# FinalSchematic_FrankensToy_FabAcademy201.net
KiCad netlist of a schematic drawn in EAGLE
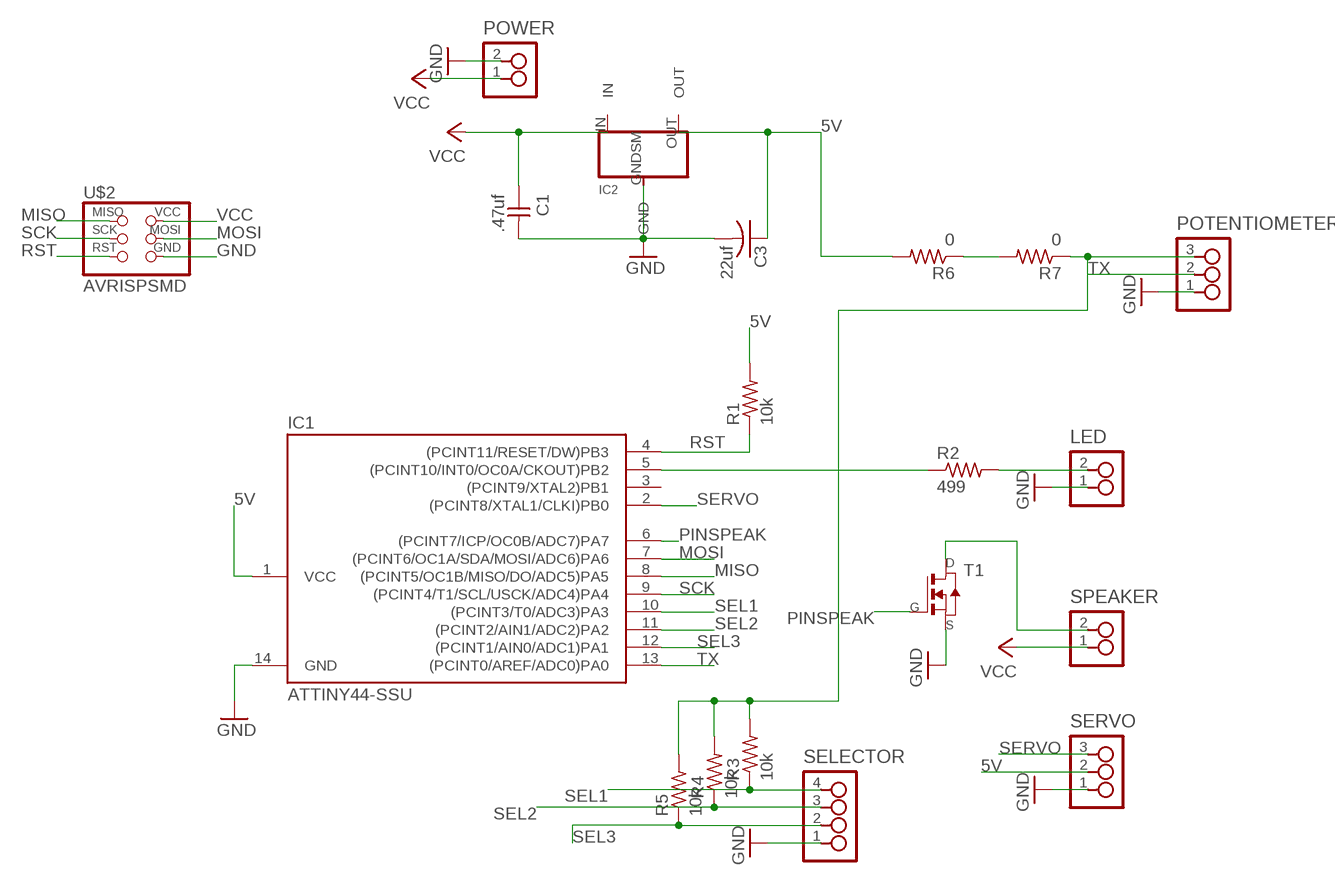
[diagram p0: schematic, sheet 1]

(export (version "E")
  (design (tool "Eeschema 10.0.6"))
  (components
    (comp (ref "C1")
      (value ".47uf")
      (footprint "eagle-import:1206")
      (libsource (lib "eagle-import") (part "UNPOLARIZED_CAPACITOR1206"))
    )
    (comp (ref "C3")
      (value "22uf")
      (footprint "eagle-import:C1206")
      (libsource (lib "eagle-import") (part "C-USC1206"))
    )
    (comp (ref "IC1")
      (value "ATTINY44-SSU")
      (footprint "eagle-import:SOIC14")
      (libsource (lib "eagle-import") (part "ATTINY44-SSU"))
    )
    (comp (ref "IC2")
      (value "REGULATOR")
      (footprint "eagle-import:SOT223")
      (libsource (lib "eagle-import") (part "REGULATOR"))
    )
    (comp (ref "LED")
      (value "2_PIN_HEADERHEADER")
      (footprint "eagle-import:SMT_PINS_2")
      (libsource (lib "eagle-import") (part "2_PIN_HEADERHEADER"))
    )
    (comp (ref "POTENTIOMETER")
      (value "3_PIN_HEADERHEADER")
      (footprint "eagle-import:SMT_PINS_3")
      (libsource (lib "eagle-import") (part "3_PIN_HEADERHEADER"))
    )
    (comp (ref "POWER")
      (value "2_PIN_HEADERHEADER")
      (footprint "eagle-import:SMT_PINS_2")
      (libsource (lib "eagle-import") (part "2_PIN_HEADERHEADER"))
    )
    (comp (ref "R1")
      (value "10k")
      (footprint "eagle-import:R1206")
      (libsource (lib "eagle-import") (part "R-US_R1206"))
    )
    (comp (ref "R2")
      (value "499")
      (footprint "eagle-import:1206")
      (libsource (lib "eagle-import") (part "RESISTOR1206"))
    )
    (comp (ref "R3")
      (value "10k")
      (footprint "eagle-import:R1206")
      (libsource (lib "eagle-import") (part "R-US_R1206"))
    )
    (comp (ref "R4")
      (value "10k")
      (footprint "eagle-import:R1206")
      (libsource (lib "eagle-import") (part "R-US_R1206"))
    )
    (comp (ref "R5")
      (value "10k")
      (footprint "eagle-import:R1206")
      (libsource (lib "eagle-import") (part "R-US_R1206"))
    )
    (comp (ref "R6")
      (value "0")
      (footprint "eagle-import:R1206")
      (libsource (lib "eagle-import") (part "R-US_R1206"))
    )
    (comp (ref "R7")
      (value "0")
      (footprint "eagle-import:R1206")
      (libsource (lib "eagle-import") (part "R-US_R1206"))
    )
    (comp (ref "SELECTOR")
      (value "4_PIN_HEADERHEADER")
      (footprint "eagle-import:SMT_PINS_4")
      (libsource (lib "eagle-import") (part "4_PIN_HEADERHEADER"))
    )
    (comp (ref "SERVO")
      (value "3_PIN_HEADERHEADER")
      (footprint "eagle-import:SMT_PINS_3")
      (libsource (lib "eagle-import") (part "3_PIN_HEADERHEADER"))
    )
    (comp (ref "SPEAKER")
      (value "2_PIN_HEADERHEADER")
      (footprint "eagle-import:SMT_PINS_2")
      (libsource (lib "eagle-import") (part "2_PIN_HEADERHEADER"))
    )
    (comp (ref "T1")
      (value "NMOSFETSOT23")
      (footprint "eagle-import:SOT-23")
      (libsource (lib "eagle-import") (part "NMOSFETSOT23"))
    )
    (comp (ref "U$2")
      (value "AVRISPSMD")
      (footprint "eagle-import:2X03SMD")
      (libsource (lib "eagle-import") (part "AVRISPSMD"))
    )
  )
  (nets
    (net (code "1") (name "/5V") (class "Default")
      (node (ref "C3") (pin "1") (pinfunction "1_1") (pintype "passive"))
      (node (ref "IC1") (pin "1") (pinfunction "VCC_1") (pintype "power_in"))
      (node (ref "IC2") (pin "OUT") (pinfunction "OUT_OUT") (pintype "bidirectional"))
      (node (ref "R1") (pin "2") (pinfunction "2_2") (pintype "passive"))
      (node (ref "R6") (pin "2") (pinfunction "2_2") (pintype "passive"))
      (node (ref "SERVO") (pin "2") (pinfunction "P$2_2") (pintype "bidirectional"))
    )
    (net (code "2") (name "/MISO") (class "Default")
      (node (ref "IC1") (pin "8") (pinfunction "(PCINT5/OC1B/MISO/DO/ADC5)PA5_8") (pintype "bidirectional"))
      (node (ref "U$2") (pin "1") (pinfunction "MISO_1") (pintype "passive"))
    )
    (net (code "3") (name "/MOSI") (class "Default")
      (node (ref "IC1") (pin "7") (pinfunction "(PCINT6/OC1A/SDA/MOSI/ADC6)PA6_7") (pintype "bidirectional"))
      (node (ref "U$2") (pin "4") (pinfunction "MOSI_4") (pintype "passive"))
    )
    (net (code "4") (name "/PINSPEAK") (class "Default")
      (node (ref "IC1") (pin "6") (pinfunction "(PCINT7/ICP/OC0B/ADC7)PA7_6") (pintype "bidirectional"))
      (node (ref "T1") (pin "3") (pinfunction "G_3") (pintype "passive"))
    )
    (net (code "5") (name "/RST") (class "Default")
      (node (ref "IC1") (pin "4") (pinfunction "(PCINT11/RESET/DW)PB3_4") (pintype "bidirectional"))
      (node (ref "R1") (pin "1") (pinfunction "1_1") (pintype "passive"))
      (node (ref "U$2") (pin "5") (pinfunction "RST_5") (pintype "passive"))
    )
    (net (code "6") (name "/SCK") (class "Default")
      (node (ref "IC1") (pin "9") (pinfunction "(PCINT4/T1/SCL/USCK/ADC4)PA4_9") (pintype "bidirectional"))
      (node (ref "U$2") (pin "3") (pinfunction "SCK_3") (pintype "passive"))
    )
    (net (code "7") (name "/SEL1") (class "Default")
      (node (ref "IC1") (pin "10") (pinfunction "(PCINT3/T0/ADC3)PA3_10") (pintype "bidirectional"))
      (node (ref "R3") (pin "1") (pinfunction "1_1") (pintype "passive"))
      (node (ref "SELECTOR") (pin "4") (pinfunction "P$4_4") (pintype "bidirectional"))
    )
    (net (code "8") (name "/SEL2") (class "Default")
      (node (ref "IC1") (pin "11") (pinfunction "(PCINT2/AIN1/ADC2)PA2_11") (pintype "bidirectional"))
      (node (ref "R4") (pin "1") (pinfunction "1_1") (pintype "passive"))
      (node (ref "SELECTOR") (pin "3") (pinfunction "P$3_3") (pintype "bidirectional"))
    )
    (net (code "9") (name "/SEL3") (class "Default")
      (node (ref "IC1") (pin "12") (pinfunction "(PCINT1/AIN0/ADC1)PA1_12") (pintype "bidirectional"))
      (node (ref "R5") (pin "1") (pinfunction "1_1") (pintype "passive"))
      (node (ref "SELECTOR") (pin "2") (pinfunction "P$2_2") (pintype "bidirectional"))
    )
    (net (code "10") (name "/SERVO") (class "Default")
      (node (ref "IC1") (pin "2") (pinfunction "(PCINT8/XTAL1/CLKI)PB0_2") (pintype "bidirectional"))
      (node (ref "SERVO") (pin "3") (pinfunction "P$3_3") (pintype "bidirectional"))
    )
    (net (code "11") (name "/TX") (class "Default")
      (node (ref "IC1") (pin "13") (pinfunction "(PCINT0/AREF/ADC0)PA0_13") (pintype "bidirectional"))
      (node (ref "POTENTIOMETER") (pin "2") (pinfunction "P$2_2") (pintype "bidirectional"))
    )
    (net (code "12") (name "GND") (class "Default")
      (node (ref "C1") (pin "2") (pinfunction "2_2") (pintype "passive"))
      (node (ref "C3") (pin "2") (pinfunction "2_2") (pintype "passive"))
      (node (ref "IC1") (pin "14") (pinfunction "GND_14") (pintype "power_in"))
      (node (ref "IC2") (pin "GNDSM") (pinfunction "GND_GNDSM") (pintype "bidirectional"))
      (node (ref "LED") (pin "1") (pinfunction "1_1") (pintype "bidirectional"))
      (node (ref "POTENTIOMETER") (pin "1") (pinfunction "P$1_1") (pintype "bidirectional"))
      (node (ref "POWER") (pin "2") (pinfunction "2_2") (pintype "bidirectional"))
      (node (ref "SELECTOR") (pin "1") (pinfunction "P$1_1") (pintype "bidirectional"))
      (node (ref "SERVO") (pin "1") (pinfunction "P$1_1") (pintype "bidirectional"))
      (node (ref "T1") (pin "2") (pinfunction "S_2") (pintype "passive"))
      (node (ref "U$2") (pin "6") (pinfunction "GND_6") (pintype "passive"))
    )
    (net (code "13") (name "Net-(IC1-(PCINT10{slash}INT0{slash}OC0A{slash}CKOUT)PB2)") (class "Default")
      (node (ref "IC1") (pin "5") (pinfunction "(PCINT10/INT0/OC0A/CKOUT)PB2_5") (pintype "bidirectional"))
      (node (ref "R2") (pin "1") (pinfunction "1_1") (pintype "passive"))
    )
    (net (code "14") (name "Net-(LED-Pad2)") (class "Default")
      (node (ref "LED") (pin "2") (pinfunction "2_2") (pintype "bidirectional"))
      (node (ref "R2") (pin "2") (pinfunction "2_2") (pintype "passive"))
    )
    (net (code "15") (name "Net-(POTENTIOMETER-P$3)") (class "Default")
      (node (ref "POTENTIOMETER") (pin "3") (pinfunction "P$3_3") (pintype "bidirectional"))
      (node (ref "R3") (pin "2") (pinfunction "2_2") (pintype "passive"))
      (node (ref "R4") (pin "2") (pinfunction "2_2") (pintype "passive"))
      (node (ref "R5") (pin "2") (pinfunction "2_2") (pintype "passive"))
      (node (ref "R7") (pin "1") (pinfunction "1_1") (pintype "passive"))
    )
    (net (code "16") (name "Net-(R6-Pad1)") (class "Default")
      (node (ref "R6") (pin "1") (pinfunction "1_1") (pintype "passive"))
      (node (ref "R7") (pin "2") (pinfunction "2_2") (pintype "passive"))
    )
    (net (code "17") (name "Net-(T1-D)") (class "Default")
      (node (ref "SPEAKER") (pin "2") (pinfunction "2_2") (pintype "bidirectional"))
      (node (ref "T1") (pin "1") (pinfunction "D_1") (pintype "passive"))
    )
    (net (code "18") (name "VCC") (class "Default")
      (node (ref "C1") (pin "1") (pinfunction "1_1") (pintype "passive"))
      (node (ref "IC2") (pin "IN") (pinfunction "IN_IN") (pintype "bidirectional"))
      (node (ref "POWER") (pin "1") (pinfunction "1_1") (pintype "bidirectional"))
      (node (ref "SPEAKER") (pin "1") (pinfunction "1_1") (pintype "bidirectional"))
      (node (ref "U$2") (pin "2") (pinfunction "VCC_2") (pintype "passive"))
    )
    (net (code "19") (name "unconnected-(IC1-(PCINT9{slash}XTAL2)PB1-Pad3)") (class "Default")
      (node (ref "IC1") (pin "3") (pinfunction "(PCINT9/XTAL2)PB1_3") (pintype "bidirectional"))
    )
  )
)
